# 14_RK3588_USB30_USB20_Ctrl.net
KiCad netlist of a schematic drawn in Altium Designer
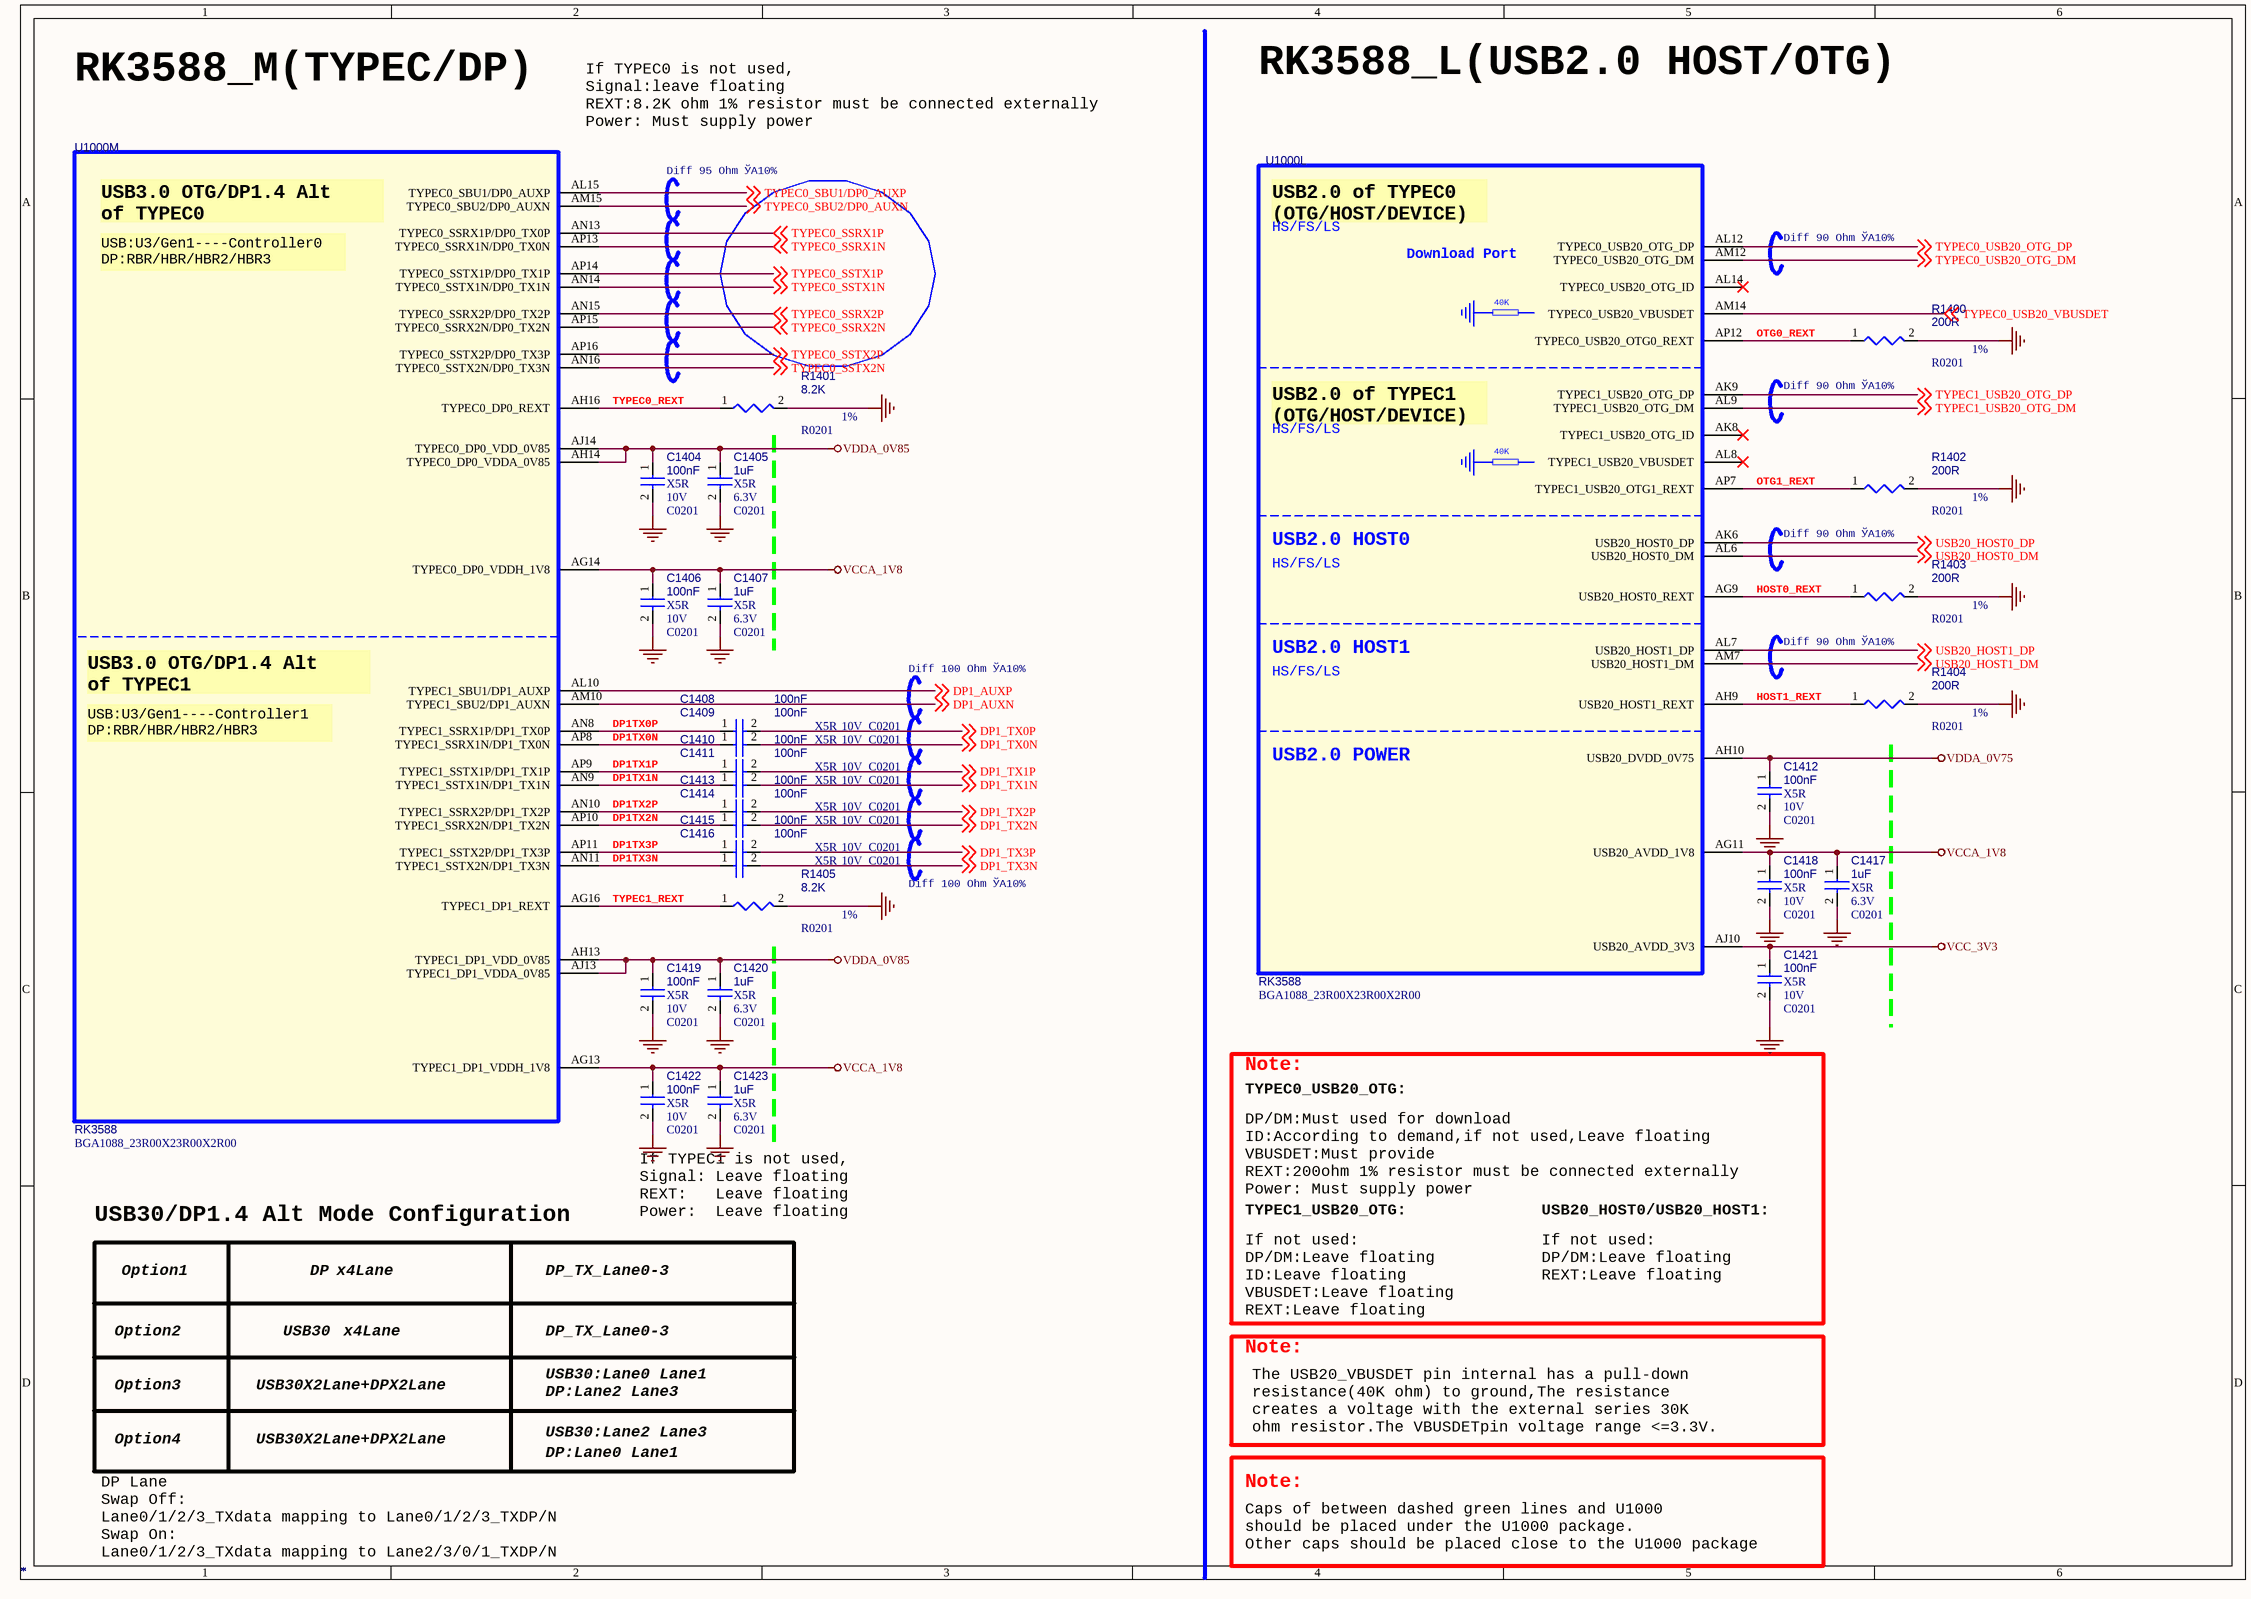
[diagram p0: 14.RK3588_USB30_USB20_Ctrl.SchDoc]

(export (version "E")
  (design (tool "Eeschema 10.0.6"))
  (components
    (comp (ref "C1404")
      (value "*")
      (footprint "C0201")
      (description "cap,100.00nF,+/-10%,10V,X5R,C0201")
      (fields
        (field (name "VOLTAGE") "10V")
        (field (name "PCB FOOTPRINT") "C0201")
        (field (name "DIELECTRIC") "X5R")
        (field (name "TOLERANCE") "10%")
        (field (name "MANUFACTURER") "TDK")
        (field (name "ALTIUM_UNNAMED_1") "100nF")
        (field (name "CREATED BY") "JJJ")
      )
      (libsource (lib "*") (part "CAP NP"))
    )
    (comp (ref "C1405")
      (value "*")
      (footprint "C0201")
      (description "cap,1.00uF,+/-20%,6.3V,X5R,C0201")
      (fields
        (field (name "VOLTAGE") "6.3V")
        (field (name "PCB FOOTPRINT") "C0201")
        (field (name "DIELECTRIC") "X5R")
        (field (name "MANUFACTURER") "TDK")
        (field (name "TOLERANCE") "20%")
        (field (name "ALTIUM_UNNAMED_1") "1uF")
        (field (name "CREATED BY") "JJJ")
      )
      (libsource (lib "*") (part "CAP NP"))
    )
    (comp (ref "C1406")
      (value "*")
      (footprint "C0201")
      (description "cap,100.00nF,+/-10%,10V,X5R,C0201")
      (fields
        (field (name "VOLTAGE") "10V")
        (field (name "PCB FOOTPRINT") "C0201")
        (field (name "DIELECTRIC") "X5R")
        (field (name "TOLERANCE") "10%")
        (field (name "MANUFACTURER") "TDK")
        (field (name "ALTIUM_UNNAMED_1") "100nF")
        (field (name "CREATED BY") "JJJ")
      )
      (libsource (lib "*") (part "CAP NP"))
    )
    (comp (ref "C1407")
      (value "*")
      (footprint "C0201")
      (description "cap,1.00uF,+/-20%,6.3V,X5R,C0201")
      (fields
        (field (name "VOLTAGE") "6.3V")
        (field (name "PCB FOOTPRINT") "C0201")
        (field (name "DIELECTRIC") "X5R")
        (field (name "MANUFACTURER") "TDK")
        (field (name "TOLERANCE") "20%")
        (field (name "ALTIUM_UNNAMED_1") "1uF")
        (field (name "CREATED BY") "JJJ")
      )
      (libsource (lib "*") (part "CAP NP"))
    )
    (comp (ref "C1408")
      (value "*")
      (footprint "C0201")
      (description "cap,100.00nF,+/-10%,10V,X5R,C0201")
      (fields
        (field (name "VOLTAGE") "10V")
        (field (name "PCB FOOTPRINT") "C0201")
        (field (name "DIELECTRIC") "X5R")
        (field (name "TOLERANCE") "10%")
        (field (name "MANUFACTURER") "TDK")
        (field (name "ALTIUM_UNNAMED_1") "100nF")
        (field (name "CREATED BY") "JJJ")
      )
      (libsource (lib "*") (part "CAP NP"))
    )
    (comp (ref "C1409")
      (value "*")
      (footprint "C0201")
      (description "cap,100.00nF,+/-10%,10V,X5R,C0201")
      (fields
        (field (name "VOLTAGE") "10V")
        (field (name "PCB FOOTPRINT") "C0201")
        (field (name "DIELECTRIC") "X5R")
        (field (name "MANUFACTURER") "TDK")
        (field (name "TOLERANCE") "10%")
        (field (name "ALTIUM_UNNAMED_1") "100nF")
        (field (name "CREATED BY") "JJJ")
      )
      (libsource (lib "*") (part "CAP NP"))
    )
    (comp (ref "C1410")
      (value "*")
      (footprint "C0201")
      (description "cap,100.00nF,+/-10%,10V,X5R,C0201")
      (fields
        (field (name "VOLTAGE") "10V")
        (field (name "PCB FOOTPRINT") "C0201")
        (field (name "DIELECTRIC") "X5R")
        (field (name "TOLERANCE") "10%")
        (field (name "MANUFACTURER") "TDK")
        (field (name "ALTIUM_UNNAMED_1") "100nF")
        (field (name "CREATED BY") "JJJ")
      )
      (libsource (lib "*") (part "CAP NP"))
    )
    (comp (ref "C1411")
      (value "*")
      (footprint "C0201")
      (description "cap,100.00nF,+/-10%,10V,X5R,C0201")
      (fields
        (field (name "VOLTAGE") "10V")
        (field (name "PCB FOOTPRINT") "C0201")
        (field (name "DIELECTRIC") "X5R")
        (field (name "MANUFACTURER") "TDK")
        (field (name "TOLERANCE") "10%")
        (field (name "ALTIUM_UNNAMED_1") "100nF")
        (field (name "CREATED BY") "JJJ")
      )
      (libsource (lib "*") (part "CAP NP"))
    )
    (comp (ref "C1412")
      (value "*")
      (footprint "C0201")
      (description "cap,100.00nF,+/-10%,10V,X5R,C0201")
      (fields
        (field (name "VOLTAGE") "10V")
        (field (name "PCB FOOTPRINT") "C0201")
        (field (name "DIELECTRIC") "X5R")
        (field (name "MANUFACTURER") "TDK")
        (field (name "TOLERANCE") "10%")
        (field (name "ALTIUM_UNNAMED_1") "100nF")
        (field (name "CREATED BY") "JJJ")
      )
      (libsource (lib "*") (part "CAP NP"))
    )
    (comp (ref "C1413")
      (value "*")
      (footprint "C0201")
      (description "cap,100.00nF,+/-10%,10V,X5R,C0201")
      (fields
        (field (name "VOLTAGE") "10V")
        (field (name "PCB FOOTPRINT") "C0201")
        (field (name "DIELECTRIC") "X5R")
        (field (name "TOLERANCE") "10%")
        (field (name "MANUFACTURER") "TDK")
        (field (name "ALTIUM_UNNAMED_1") "100nF")
        (field (name "CREATED BY") "JJJ")
      )
      (libsource (lib "*") (part "CAP NP"))
    )
    (comp (ref "C1414")
      (value "*")
      (footprint "C0201")
      (description "cap,100.00nF,+/-10%,10V,X5R,C0201")
      (fields
        (field (name "VOLTAGE") "10V")
        (field (name "PCB FOOTPRINT") "C0201")
        (field (name "DIELECTRIC") "X5R")
        (field (name "MANUFACTURER") "TDK")
        (field (name "TOLERANCE") "10%")
        (field (name "ALTIUM_UNNAMED_1") "100nF")
        (field (name "CREATED BY") "JJJ")
      )
      (libsource (lib "*") (part "CAP NP"))
    )
    (comp (ref "C1415")
      (value "*")
      (footprint "C0201")
      (description "cap,100.00nF,+/-10%,10V,X5R,C0201")
      (fields
        (field (name "VOLTAGE") "10V")
        (field (name "PCB FOOTPRINT") "C0201")
        (field (name "DIELECTRIC") "X5R")
        (field (name "TOLERANCE") "10%")
        (field (name "MANUFACTURER") "TDK")
        (field (name "ALTIUM_UNNAMED_1") "100nF")
        (field (name "CREATED BY") "JJJ")
      )
      (libsource (lib "*") (part "CAP NP"))
    )
    (comp (ref "C1416")
      (value "*")
      (footprint "C0201")
      (description "cap,100.00nF,+/-10%,10V,X5R,C0201")
      (fields
        (field (name "VOLTAGE") "10V")
        (field (name "PCB FOOTPRINT") "C0201")
        (field (name "DIELECTRIC") "X5R")
        (field (name "MANUFACTURER") "TDK")
        (field (name "TOLERANCE") "10%")
        (field (name "ALTIUM_UNNAMED_1") "100nF")
        (field (name "CREATED BY") "JJJ")
      )
      (libsource (lib "*") (part "CAP NP"))
    )
    (comp (ref "C1417")
      (value "*")
      (footprint "C0201")
      (description "cap,1.00uF,+/-20%,6.3V,X5R,C0201")
      (fields
        (field (name "VOLTAGE") "6.3V")
        (field (name "PCB FOOTPRINT") "C0201")
        (field (name "DIELECTRIC") "X5R")
        (field (name "TOLERANCE") "20%")
        (field (name "MANUFACTURER") "TDK")
        (field (name "ALTIUM_UNNAMED_1") "1uF")
        (field (name "CREATED BY") "JJJ")
      )
      (libsource (lib "*") (part "CAP NP"))
    )
    (comp (ref "C1418")
      (value "*")
      (footprint "C0201")
      (description "cap,100.00nF,+/-10%,10V,X5R,C0201")
      (fields
        (field (name "VOLTAGE") "10V")
        (field (name "PCB FOOTPRINT") "C0201")
        (field (name "DIELECTRIC") "X5R")
        (field (name "MANUFACTURER") "TDK")
        (field (name "TOLERANCE") "10%")
        (field (name "ALTIUM_UNNAMED_1") "100nF")
        (field (name "CREATED BY") "JJJ")
      )
      (libsource (lib "*") (part "CAP NP"))
    )
    (comp (ref "C1419")
      (value "*")
      (footprint "C0201")
      (description "cap,100.00nF,+/-10%,10V,X5R,C0201")
      (fields
        (field (name "VOLTAGE") "10V")
        (field (name "PCB FOOTPRINT") "C0201")
        (field (name "DIELECTRIC") "X5R")
        (field (name "TOLERANCE") "10%")
        (field (name "MANUFACTURER") "TDK")
        (field (name "ALTIUM_UNNAMED_1") "100nF")
        (field (name "CREATED BY") "JJJ")
      )
      (libsource (lib "*") (part "CAP NP"))
    )
    (comp (ref "C1420")
      (value "*")
      (footprint "C0201")
      (description "cap,1.00uF,+/-20%,6.3V,X5R,C0201")
      (fields
        (field (name "VOLTAGE") "6.3V")
        (field (name "PCB FOOTPRINT") "C0201")
        (field (name "DIELECTRIC") "X5R")
        (field (name "MANUFACTURER") "TDK")
        (field (name "TOLERANCE") "20%")
        (field (name "ALTIUM_UNNAMED_1") "1uF")
        (field (name "CREATED BY") "JJJ")
      )
      (libsource (lib "*") (part "CAP NP"))
    )
    (comp (ref "C1421")
      (value "*")
      (footprint "C0201")
      (description "cap,100.00nF,+/-10%,10V,X5R,C0201")
      (fields
        (field (name "VOLTAGE") "10V")
        (field (name "PCB FOOTPRINT") "C0201")
        (field (name "DIELECTRIC") "X5R")
        (field (name "MANUFACTURER") "TDK")
        (field (name "TOLERANCE") "10%")
        (field (name "ALTIUM_UNNAMED_1") "100nF")
        (field (name "CREATED BY") "JJJ")
      )
      (libsource (lib "*") (part "CAP NP"))
    )
    (comp (ref "C1422")
      (value "*")
      (footprint "C0201")
      (description "cap,100.00nF,+/-10%,10V,X5R,C0201")
      (fields
        (field (name "VOLTAGE") "10V")
        (field (name "PCB FOOTPRINT") "C0201")
        (field (name "DIELECTRIC") "X5R")
        (field (name "TOLERANCE") "10%")
        (field (name "MANUFACTURER") "TDK")
        (field (name "ALTIUM_UNNAMED_1") "100nF")
        (field (name "CREATED BY") "JJJ")
      )
      (libsource (lib "*") (part "CAP NP"))
    )
    (comp (ref "C1423")
      (value "*")
      (footprint "C0201")
      (description "cap,1.00uF,+/-20%,6.3V,X5R,C0201")
      (fields
        (field (name "VOLTAGE") "6.3V")
        (field (name "PCB FOOTPRINT") "C0201")
        (field (name "DIELECTRIC") "X5R")
        (field (name "MANUFACTURER") "TDK")
        (field (name "TOLERANCE") "20%")
        (field (name "ALTIUM_UNNAMED_1") "1uF")
        (field (name "CREATED BY") "JJJ")
      )
      (libsource (lib "*") (part "CAP NP"))
    )
    (comp (ref "R1400")
      (value "*")
      (footprint "R0402")
      (description "НЁУГєсД¤µзЧи,200R,+/-1%,R0201,1/20W.")
      (fields
        (field (name "PCB FOOTPRINT") "R0201")
        (field (name "TOLERANCE") "1%")
        (field (name "MANUFACTURER") "YAGEO")
        (field (name "ALTIUM_UNNAMED_1") "200R")
        (field (name "CREATED BY") "YTL")
      )
      (libsource (lib "*") (part "RESISTOR_Dup1"))
    )
    (comp (ref "R1401")
      (value "*")
      (footprint "R0402")
      (description "НЁУГєсД¤µзЧи,8K2,+/-1%,R0201,1/20W.")
      (fields
        (field (name "PCB FOOTPRINT") "R0201")
        (field (name "TOLERANCE") "1%")
        (field (name "MANUFACTURER") "YAGEO")
        (field (name "ALTIUM_UNNAMED_1") "8.2K")
        (field (name "CREATED BY") "YTL")
      )
      (libsource (lib "*") (part "RESISTOR_Dup1"))
    )
    (comp (ref "R1402")
      (value "*")
      (footprint "R0402")
      (description "НЁУГєсД¤µзЧи,200R,+/-1%,R0201,1/20W.")
      (fields
        (field (name "PCB FOOTPRINT") "R0201")
        (field (name "TOLERANCE") "1%")
        (field (name "MANUFACTURER") "YAGEO")
        (field (name "ALTIUM_UNNAMED_1") "200R")
        (field (name "CREATED BY") "YTL")
      )
      (libsource (lib "*") (part "RESISTOR_Dup1"))
    )
    (comp (ref "R1403")
      (value "*")
      (footprint "R0402")
      (description "НЁУГєсД¤µзЧи,200R,+/-1%,R0201,1/20W.")
      (fields
        (field (name "PCB FOOTPRINT") "R0201")
        (field (name "TOLERANCE") "1%")
        (field (name "MANUFACTURER") "YAGEO")
        (field (name "ALTIUM_UNNAMED_1") "200R")
        (field (name "CREATED BY") "YTL")
      )
      (libsource (lib "*") (part "RESISTOR_Dup1"))
    )
    (comp (ref "R1404")
      (value "*")
      (footprint "R0402")
      (description "НЁУГєсД¤µзЧи,200R,+/-1%,R0201,1/20W.")
      (fields
        (field (name "PCB FOOTPRINT") "R0201")
        (field (name "TOLERANCE") "1%")
        (field (name "MANUFACTURER") "YAGEO")
        (field (name "ALTIUM_UNNAMED_1") "200R")
        (field (name "CREATED BY") "YTL")
      )
      (libsource (lib "*") (part "RESISTOR_Dup1"))
    )
    (comp (ref "R1405")
      (value "*")
      (footprint "R0402")
      (description "НЁУГєсД¤µзЧи,8K2,+/-1%,R0201,1/20W.")
      (fields
        (field (name "PCB FOOTPRINT") "R0201")
        (field (name "TOLERANCE") "1%")
        (field (name "MANUFACTURER") "YAGEO")
        (field (name "ALTIUM_UNNAMED_1") "8.2K")
        (field (name "CREATED BY") "YTL")
      )
      (libsource (lib "*") (part "RESISTOR_Dup1"))
    )
    (comp (ref "U1000")
      (value "*")
      (footprint "BGA1088_23R00X23R00X2R00")
      (description "ROCKCHIP SOC")
      (fields
        (field (name "MANUFACTURER") "Rockchip (ИрРѕОў)")
        (field (name "PCB FOOTPRINT") "BGA1088_23R00X23R00X2R00")
        (field (name "ALTIUM_UNNAMED_1") "RK3588")
        (field (name "CREATED BY") "YWQ")
      )
      (libsource (lib "*") (part "SOC_RK3588"))
    )
  )
  (nets
    (net (code "1") (name "/DP1TX0N") (class "Default")
      (node (ref "C1409") (pin "1") (pinfunction "1_1") (pintype "passive"))
      (node (ref "U1000") (pin "AP8") (pinfunction "TYPEC1_SSRX1N/DP1_TX0N_AP8") (pintype "passive"))
    )
    (net (code "2") (name "/DP1TX0P") (class "Default")
      (node (ref "C1408") (pin "1") (pinfunction "1_1") (pintype "passive"))
      (node (ref "U1000") (pin "AN8") (pinfunction "TYPEC1_SSRX1P/DP1_TX0P_AN8") (pintype "passive"))
    )
    (net (code "3") (name "/DP1TX1N") (class "Default")
      (node (ref "C1411") (pin "1") (pinfunction "1_1") (pintype "passive"))
      (node (ref "U1000") (pin "AN9") (pinfunction "TYPEC1_SSTX1N/DP1_TX1N_AN9") (pintype "passive"))
    )
    (net (code "4") (name "/DP1TX1P") (class "Default")
      (node (ref "C1410") (pin "1") (pinfunction "1_1") (pintype "passive"))
      (node (ref "U1000") (pin "AP9") (pinfunction "TYPEC1_SSTX1P/DP1_TX1P_AP9") (pintype "passive"))
    )
    (net (code "5") (name "/DP1TX2N") (class "Default")
      (node (ref "C1414") (pin "1") (pinfunction "1_1") (pintype "passive"))
      (node (ref "U1000") (pin "AP10") (pinfunction "TYPEC1_SSRX2N/DP1_TX2N_AP10") (pintype "passive"))
    )
    (net (code "6") (name "/DP1TX2P") (class "Default")
      (node (ref "C1413") (pin "1") (pinfunction "1_1") (pintype "passive"))
      (node (ref "U1000") (pin "AN10") (pinfunction "TYPEC1_SSRX2P/DP1_TX2P_AN10") (pintype "passive"))
    )
    (net (code "7") (name "/DP1TX3N") (class "Default")
      (node (ref "C1416") (pin "1") (pinfunction "1_1") (pintype "passive"))
      (node (ref "U1000") (pin "AN11") (pinfunction "TYPEC1_SSTX2N/DP1_TX3N_AN11") (pintype "passive"))
    )
    (net (code "8") (name "/DP1TX3P") (class "Default")
      (node (ref "C1415") (pin "1") (pinfunction "1_1") (pintype "passive"))
      (node (ref "U1000") (pin "AP11") (pinfunction "TYPEC1_SSTX2P/DP1_TX3P_AP11") (pintype "passive"))
    )
    (net (code "9") (name "/HOST0_REXT") (class "Default")
      (node (ref "R1403") (pin "1") (pinfunction "1_1") (pintype "passive"))
      (node (ref "U1000") (pin "AG9") (pinfunction "USB20_HOST0_REXT_AG9") (pintype "passive"))
    )
    (net (code "10") (name "/HOST1_REXT") (class "Default")
      (node (ref "R1404") (pin "1") (pinfunction "1_1") (pintype "passive"))
      (node (ref "U1000") (pin "AH9") (pinfunction "USB20_HOST1_REXT_AH9") (pintype "passive"))
    )
    (net (code "11") (name "/OTG0_REXT") (class "Default")
      (node (ref "R1400") (pin "1") (pinfunction "1_1") (pintype "passive"))
      (node (ref "U1000") (pin "AP12") (pinfunction "TYPEC0_USB20_OTG0_REXT_AP12") (pintype "passive"))
    )
    (net (code "12") (name "/OTG1_REXT") (class "Default")
      (node (ref "R1402") (pin "1") (pinfunction "1_1") (pintype "passive"))
      (node (ref "U1000") (pin "AP7") (pinfunction "TYPEC1_USB20_OTG1_REXT_AP7") (pintype "passive"))
    )
    (net (code "13") (name "/TYPEC0_REXT") (class "Default")
      (node (ref "R1401") (pin "1") (pinfunction "1_1") (pintype "passive"))
      (node (ref "U1000") (pin "AH16") (pinfunction "TYPEC0_DP0_REXT_AH16") (pintype "passive"))
    )
    (net (code "14") (name "/TYPEC1_REXT") (class "Default")
      (node (ref "R1405") (pin "1") (pinfunction "1_1") (pintype "passive"))
      (node (ref "U1000") (pin "AG16") (pinfunction "TYPEC1_DP1_REXT_AG16") (pintype "passive"))
    )
    (net (code "15") (name "DP1_AUXN") (class "Default")
      (node (ref "U1000") (pin "AM10") (pinfunction "TYPEC1_SBU2/DP1_AUXN_AM10") (pintype "passive"))
    )
    (net (code "16") (name "DP1_AUXP") (class "Default")
      (node (ref "U1000") (pin "AL10") (pinfunction "TYPEC1_SBU1/DP1_AUXP_AL10") (pintype "passive"))
    )
    (net (code "17") (name "DP1_TX0N") (class "Default")
      (node (ref "C1409") (pin "2") (pinfunction "2_2") (pintype "passive"))
    )
    (net (code "18") (name "DP1_TX0P") (class "Default")
      (node (ref "C1408") (pin "2") (pinfunction "2_2") (pintype "passive"))
    )
    (net (code "19") (name "DP1_TX1N") (class "Default")
      (node (ref "C1411") (pin "2") (pinfunction "2_2") (pintype "passive"))
    )
    (net (code "20") (name "DP1_TX1P") (class "Default")
      (node (ref "C1410") (pin "2") (pinfunction "2_2") (pintype "passive"))
    )
    (net (code "21") (name "DP1_TX2N") (class "Default")
      (node (ref "C1414") (pin "2") (pinfunction "2_2") (pintype "passive"))
    )
    (net (code "22") (name "DP1_TX2P") (class "Default")
      (node (ref "C1413") (pin "2") (pinfunction "2_2") (pintype "passive"))
    )
    (net (code "23") (name "DP1_TX3N") (class "Default")
      (node (ref "C1416") (pin "2") (pinfunction "2_2") (pintype "passive"))
    )
    (net (code "24") (name "DP1_TX3P") (class "Default")
      (node (ref "C1415") (pin "2") (pinfunction "2_2") (pintype "passive"))
    )
    (net (code "25") (name "GND") (class "Default")
      (node (ref "C1404") (pin "2") (pinfunction "2_2") (pintype "passive"))
      (node (ref "C1405") (pin "2") (pinfunction "2_2") (pintype "passive"))
      (node (ref "C1406") (pin "2") (pinfunction "2_2") (pintype "passive"))
      (node (ref "C1407") (pin "2") (pinfunction "2_2") (pintype "passive"))
      (node (ref "C1412") (pin "2") (pinfunction "2_2") (pintype "passive"))
      (node (ref "C1417") (pin "2") (pinfunction "2_2") (pintype "passive"))
      (node (ref "C1418") (pin "2") (pinfunction "2_2") (pintype "passive"))
      (node (ref "C1419") (pin "2") (pinfunction "2_2") (pintype "passive"))
      (node (ref "C1420") (pin "2") (pinfunction "2_2") (pintype "passive"))
      (node (ref "C1421") (pin "2") (pinfunction "2_2") (pintype "passive"))
      (node (ref "C1422") (pin "2") (pinfunction "2_2") (pintype "passive"))
      (node (ref "C1423") (pin "2") (pinfunction "2_2") (pintype "passive"))
      (node (ref "R1400") (pin "2") (pinfunction "2_2") (pintype "passive"))
      (node (ref "R1401") (pin "2") (pinfunction "2_2") (pintype "passive"))
      (node (ref "R1402") (pin "2") (pinfunction "2_2") (pintype "passive"))
      (node (ref "R1403") (pin "2") (pinfunction "2_2") (pintype "passive"))
      (node (ref "R1404") (pin "2") (pinfunction "2_2") (pintype "passive"))
      (node (ref "R1405") (pin "2") (pinfunction "2_2") (pintype "passive"))
    )
    (net (code "26") (name "TYPEC0_SBU1{slash}DP0_AUXP") (class "Default")
      (node (ref "U1000") (pin "AL15") (pinfunction "TYPEC0_SBU1/DP0_AUXP_AL15") (pintype "passive"))
    )
    (net (code "27") (name "TYPEC0_SBU2{slash}DP0_AUXN") (class "Default")
      (node (ref "U1000") (pin "AM15") (pinfunction "TYPEC0_SBU2/DP0_AUXN_AM15") (pintype "passive"))
    )
    (net (code "28") (name "TYPEC0_SSRX1N") (class "Default")
      (node (ref "U1000") (pin "AP13") (pinfunction "TYPEC0_SSRX1N/DP0_TX0N_AP13") (pintype "passive"))
    )
    (net (code "29") (name "TYPEC0_SSRX1P") (class "Default")
      (node (ref "U1000") (pin "AN13") (pinfunction "TYPEC0_SSRX1P/DP0_TX0P_AN13") (pintype "passive"))
    )
    (net (code "30") (name "TYPEC0_SSRX2N") (class "Default")
      (node (ref "U1000") (pin "AP15") (pinfunction "TYPEC0_SSRX2N/DP0_TX2N_AP15") (pintype "passive"))
    )
    (net (code "31") (name "TYPEC0_SSRX2P") (class "Default")
      (node (ref "U1000") (pin "AN15") (pinfunction "TYPEC0_SSRX2P/DP0_TX2P_AN15") (pintype "passive"))
    )
    (net (code "32") (name "TYPEC0_SSTX1N") (class "Default")
      (node (ref "U1000") (pin "AN14") (pinfunction "TYPEC0_SSTX1N/DP0_TX1N_AN14") (pintype "passive"))
    )
    (net (code "33") (name "TYPEC0_SSTX1P") (class "Default")
      (node (ref "U1000") (pin "AP14") (pinfunction "TYPEC0_SSTX1P/DP0_TX1P_AP14") (pintype "passive"))
    )
    (net (code "34") (name "TYPEC0_SSTX2N") (class "Default")
      (node (ref "U1000") (pin "AN16") (pinfunction "TYPEC0_SSTX2N/DP0_TX3N_AN16") (pintype "passive"))
    )
    (net (code "35") (name "TYPEC0_SSTX2P") (class "Default")
      (node (ref "U1000") (pin "AP16") (pinfunction "TYPEC0_SSTX2P/DP0_TX3P_AP16") (pintype "passive"))
    )
    (net (code "36") (name "TYPEC0_USB20_OTG_DM") (class "Default")
      (node (ref "U1000") (pin "AM12") (pinfunction "TYPEC0_USB20_OTG_DM_AM12") (pintype "passive"))
    )
    (net (code "37") (name "TYPEC0_USB20_OTG_DP") (class "Default")
      (node (ref "U1000") (pin "AL12") (pinfunction "TYPEC0_USB20_OTG_DP_AL12") (pintype "passive"))
    )
    (net (code "38") (name "TYPEC0_USB20_VBUSDET") (class "Default")
      (node (ref "U1000") (pin "AM14") (pinfunction "TYPEC0_USB20_VBUSDET_AM14") (pintype "passive"))
    )
    (net (code "39") (name "TYPEC1_USB20_OTG_DM") (class "Default")
      (node (ref "U1000") (pin "AL9") (pinfunction "TYPEC1_USB20_OTG_DM_AL9") (pintype "passive"))
    )
    (net (code "40") (name "TYPEC1_USB20_OTG_DP") (class "Default")
      (node (ref "U1000") (pin "AK9") (pinfunction "TYPEC1_USB20_OTG_DP_AK9") (pintype "passive"))
    )
    (net (code "41") (name "USB20_HOST0_DM") (class "Default")
      (node (ref "U1000") (pin "AL6") (pinfunction "USB20_HOST0_DM_AL6") (pintype "passive"))
    )
    (net (code "42") (name "USB20_HOST0_DP") (class "Default")
      (node (ref "U1000") (pin "AK6") (pinfunction "USB20_HOST0_DP_AK6") (pintype "passive"))
    )
    (net (code "43") (name "USB20_HOST1_DM") (class "Default")
      (node (ref "U1000") (pin "AM7") (pinfunction "USB20_HOST1_DM_AM7") (pintype "passive"))
    )
    (net (code "44") (name "USB20_HOST1_DP") (class "Default")
      (node (ref "U1000") (pin "AL7") (pinfunction "USB20_HOST1_DP_AL7") (pintype "passive"))
    )
    (net (code "45") (name "VCCA_1V8") (class "Default")
      (node (ref "C1406") (pin "1") (pinfunction "1_1") (pintype "passive"))
      (node (ref "C1407") (pin "1") (pinfunction "1_1") (pintype "passive"))
      (node (ref "C1417") (pin "1") (pinfunction "1_1") (pintype "passive"))
      (node (ref "C1418") (pin "1") (pinfunction "1_1") (pintype "passive"))
      (node (ref "C1422") (pin "1") (pinfunction "1_1") (pintype "passive"))
      (node (ref "C1423") (pin "1") (pinfunction "1_1") (pintype "passive"))
      (node (ref "U1000") (pin "AG11") (pinfunction "USB20_AVDD_1V8_AG11") (pintype "passive"))
      (node (ref "U1000") (pin "AG13") (pinfunction "TYPEC1_DP1_VDDH_1V8_AG13") (pintype "passive"))
      (node (ref "U1000") (pin "AG14") (pinfunction "TYPEC0_DP0_VDDH_1V8_AG14") (pintype "passive"))
    )
    (net (code "46") (name "VCC_3V3") (class "Default")
      (node (ref "C1421") (pin "1") (pinfunction "1_1") (pintype "passive"))
      (node (ref "U1000") (pin "AJ10") (pinfunction "USB20_AVDD_3V3_AJ10") (pintype "passive"))
    )
    (net (code "47") (name "VDDA_0V75") (class "Default")
      (node (ref "C1412") (pin "1") (pinfunction "1_1") (pintype "passive"))
      (node (ref "U1000") (pin "AH10") (pinfunction "USB20_DVDD_0V75_AH10") (pintype "passive"))
    )
    (net (code "48") (name "VDDA_0V85") (class "Default")
      (node (ref "C1404") (pin "1") (pinfunction "1_1") (pintype "passive"))
      (node (ref "C1405") (pin "1") (pinfunction "1_1") (pintype "passive"))
      (node (ref "C1419") (pin "1") (pinfunction "1_1") (pintype "passive"))
      (node (ref "C1420") (pin "1") (pinfunction "1_1") (pintype "passive"))
      (node (ref "U1000") (pin "AH13") (pinfunction "TYPEC1_DP1_VDD_0V85_AH13") (pintype "passive"))
      (node (ref "U1000") (pin "AH14") (pinfunction "TYPEC0_DP0_VDDA_0V85_AH14") (pintype "passive"))
      (node (ref "U1000") (pin "AJ13") (pinfunction "TYPEC1_DP1_VDDA_0V85_AJ13") (pintype "passive"))
      (node (ref "U1000") (pin "AJ14") (pinfunction "TYPEC0_DP0_VDD_0V85_AJ14") (pintype "passive"))
    )
    (net (code "49") (name "unconnected-(U1000L-TYPEC0_USB20_OTG_ID-PadAL14)") (class "Default")
      (node (ref "U1000") (pin "AL14") (pinfunction "TYPEC0_USB20_OTG_ID_AL14") (pintype "passive+no_connect"))
    )
    (net (code "50") (name "unconnected-(U1000L-TYPEC1_USB20_OTG_ID-PadAK8)") (class "Default")
      (node (ref "U1000") (pin "AK8") (pinfunction "TYPEC1_USB20_OTG_ID_AK8") (pintype "passive+no_connect"))
    )
    (net (code "51") (name "unconnected-(U1000L-TYPEC1_USB20_VBUSDET-PadAL8)") (class "Default")
      (node (ref "U1000") (pin "AL8") (pinfunction "TYPEC1_USB20_VBUSDET_AL8") (pintype "passive+no_connect"))
    )
  )
)
